# Zigbee_Tracker_v2_Mainboard.net
KiCad netlist of a schematic drawn in EAGLE
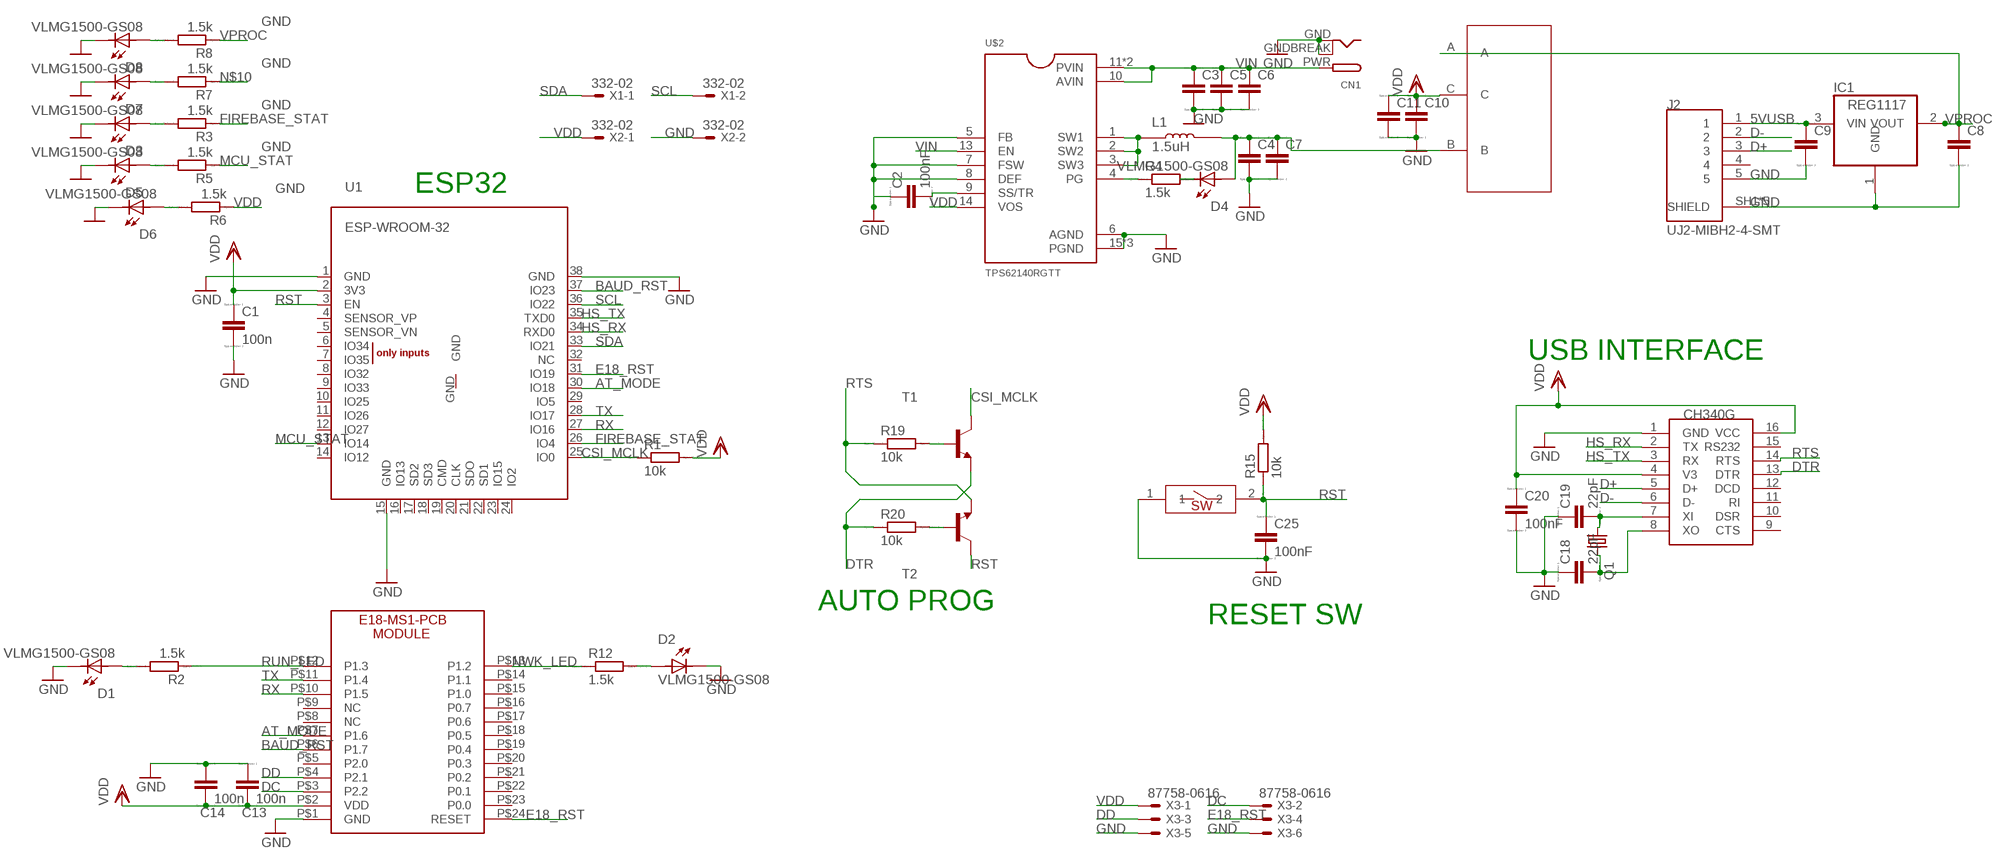
[diagram p0: schematic, sheet 1]

(export (version "E")
  (design (tool "Eeschema 10.0.6"))
  (components
    (comp (ref "C1")
      (value "100n")
      (footprint "eagle-import:C0603")
      (libsource (lib "eagle-import") (part "CC0603"))
    )
    (comp (ref "C2")
      (value "100nF")
      (footprint "eagle-import:C0402")
      (libsource (lib "eagle-import") (part "CC0402"))
    )
    (comp (ref "C3")
      (value "CC0402")
      (footprint "eagle-import:C0402")
      (libsource (lib "eagle-import") (part "CC0402"))
    )
    (comp (ref "C4")
      (value "CC0402")
      (footprint "eagle-import:C0402")
      (libsource (lib "eagle-import") (part "CC0402"))
    )
    (comp (ref "C5")
      (value "CC1210")
      (footprint "eagle-import:C1210")
      (libsource (lib "eagle-import") (part "CC1210"))
    )
    (comp (ref "C6")
      (value "CC1210")
      (footprint "eagle-import:C1210")
      (libsource (lib "eagle-import") (part "CC1210"))
    )
    (comp (ref "C7")
      (value "CC1210")
      (footprint "eagle-import:C1210")
      (libsource (lib "eagle-import") (part "CC1210"))
    )
    (comp (ref "C8")
      (value "CC0603")
      (footprint "eagle-import:C0603")
      (libsource (lib "eagle-import") (part "CC0603"))
    )
    (comp (ref "C9")
      (value "CC0603")
      (footprint "eagle-import:C0603")
      (libsource (lib "eagle-import") (part "CC0603"))
    )
    (comp (ref "C10")
      (value "CC1210")
      (footprint "eagle-import:C1210")
      (libsource (lib "eagle-import") (part "CC1210"))
    )
    (comp (ref "C11")
      (value "CC1210")
      (footprint "eagle-import:C1210")
      (libsource (lib "eagle-import") (part "CC1210"))
    )
    (comp (ref "C13")
      (value "100n")
      (footprint "eagle-import:C0603")
      (libsource (lib "eagle-import") (part "CC0603"))
    )
    (comp (ref "C14")
      (value "100n")
      (footprint "eagle-import:C0603")
      (libsource (lib "eagle-import") (part "CC0603"))
    )
    (comp (ref "C18")
      (value "22pF")
      (footprint "eagle-import:C0402")
      (libsource (lib "eagle-import") (part "CC0402"))
    )
    (comp (ref "C19")
      (value "22pF")
      (footprint "eagle-import:C0402")
      (libsource (lib "eagle-import") (part "CC0402"))
    )
    (comp (ref "C20")
      (value "100nF")
      (footprint "eagle-import:C0603")
      (libsource (lib "eagle-import") (part "CC0603"))
    )
    (comp (ref "C25")
      (value "100nF")
      (footprint "eagle-import:C0402")
      (libsource (lib "eagle-import") (part "CC0402"))
    )
    (comp (ref "CN1")
      (value "DCBARRELPTH")
      (footprint "eagle-import:DCJACK_2MM_PTH")
      (libsource (lib "eagle-import") (part "DCBARRELPTH"))
    )
    (comp (ref "D1")
      (value "VLMG1500-GS08")
      (footprint "eagle-import:LEDC1005X35N")
      (fields (field (name "MF") "Vishay"))
      (libsource (lib "eagle-import") (part "VLMG1500-GS08"))
    )
    (comp (ref "D2")
      (value "VLMG1500-GS08")
      (footprint "eagle-import:LEDC1005X35N")
      (fields (field (name "MF") "Vishay"))
      (libsource (lib "eagle-import") (part "VLMG1500-GS08"))
    )
    (comp (ref "D3")
      (value "VLMG1500-GS08")
      (footprint "eagle-import:LEDC1005X35N")
      (fields (field (name "MF") "Vishay"))
      (libsource (lib "eagle-import") (part "VLMG1500-GS08"))
    )
    (comp (ref "D4")
      (value "VLMG1500-GS08")
      (footprint "eagle-import:LEDC1005X35N")
      (fields (field (name "MF") "Vishay"))
      (libsource (lib "eagle-import") (part "VLMG1500-GS08"))
    )
    (comp (ref "D5")
      (value "VLMG1500-GS08")
      (footprint "eagle-import:LEDC1005X35N")
      (fields (field (name "MF") "Vishay"))
      (libsource (lib "eagle-import") (part "VLMG1500-GS08"))
    )
    (comp (ref "D6")
      (value "VLMG1500-GS08")
      (footprint "eagle-import:LEDC1005X35N")
      (fields (field (name "MF") "Vishay"))
      (libsource (lib "eagle-import") (part "VLMG1500-GS08"))
    )
    (comp (ref "D7")
      (value "VLMG1500-GS08")
      (footprint "eagle-import:LEDC1005X35N")
      (fields (field (name "MF") "Vishay"))
      (libsource (lib "eagle-import") (part "VLMG1500-GS08"))
    )
    (comp (ref "D8")
      (value "VLMG1500-GS08")
      (footprint "eagle-import:LEDC1005X35N")
      (fields (field (name "MF") "Vishay"))
      (libsource (lib "eagle-import") (part "VLMG1500-GS08"))
    )
    (comp (ref "IC1")
      (value "REG1117")
      (footprint "eagle-import:SOT223")
      (libsource (lib "eagle-import") (part "REG1117"))
    )
    (comp (ref "J2")
      (value "UJ2-MIBH2-4-SMT")
      (footprint "eagle-import:CUI_UJ2-MIBH2-4-SMT")
      (fields (field (name "MF") "CUI Inc."))
      (libsource (lib "eagle-import") (part "UJ2-MIBH2-4-SMT"))
    )
    (comp (ref "L1")
      (value "1.5uH")
      (footprint "eagle-import:INDC2520X120N")
      (fields (field (name "MF") "Murata Electronics") (field (name "MP") "DFE252012F-100M=P2"))
      (libsource (lib "eagle-import") (part "DFE252012F-100M=P2"))
    )
    (comp (ref "Q1")
      (value "KX-7")
      (footprint "eagle-import:3.2X2.5_KX-7")
      (libsource (lib "eagle-import") (part "KX-7"))
    )
    (comp (ref "R1")
      (value "10k")
      (footprint "eagle-import:R0402")
      (libsource (lib "eagle-import") (part "RR0402"))
    )
    (comp (ref "R2")
      (value "1.5k")
      (footprint "eagle-import:R0402")
      (libsource (lib "eagle-import") (part "RR0402"))
    )
    (comp (ref "R3")
      (value "1.5k")
      (footprint "eagle-import:R0402")
      (libsource (lib "eagle-import") (part "RR0402"))
    )
    (comp (ref "R4")
      (value "1.5k")
      (footprint "eagle-import:R0402")
      (libsource (lib "eagle-import") (part "RR0402"))
    )
    (comp (ref "R5")
      (value "1.5k")
      (footprint "eagle-import:R0402")
      (libsource (lib "eagle-import") (part "RR0402"))
    )
    (comp (ref "R6")
      (value "1.5k")
      (footprint "eagle-import:R0402")
      (libsource (lib "eagle-import") (part "RR0402"))
    )
    (comp (ref "R7")
      (value "1.5k")
      (footprint "eagle-import:R0402")
      (libsource (lib "eagle-import") (part "RR0402"))
    )
    (comp (ref "R8")
      (value "1.5k")
      (footprint "eagle-import:R0402")
      (libsource (lib "eagle-import") (part "RR0402"))
    )
    (comp (ref "R12")
      (value "1.5k")
      (footprint "eagle-import:R0402")
      (libsource (lib "eagle-import") (part "RR0402"))
    )
    (comp (ref "R15")
      (value "10k")
      (footprint "eagle-import:R0402")
      (libsource (lib "eagle-import") (part "RR0402"))
    )
    (comp (ref "R19")
      (value "10k")
      (footprint "eagle-import:R0402")
      (libsource (lib "eagle-import") (part "RR0402"))
    )
    (comp (ref "R20")
      (value "10k")
      (footprint "eagle-import:R0402")
      (libsource (lib "eagle-import") (part "RR0402"))
    )
    (comp (ref "RESET")
      (value "SMDSWITCH")
      (footprint "eagle-import:RESC4217X170")
      (libsource (lib "eagle-import") (part "SMDSWITCH"))
    )
    (comp (ref "T1")
      (value "-NPN-SOT23-BEC")
      (footprint "eagle-import:SOT23-BEC")
      (libsource (lib "eagle-import") (part "-NPN-SOT23-BEC"))
    )
    (comp (ref "T2")
      (value "-NPN-SOT23-BEC")
      (footprint "eagle-import:SOT23-BEC")
      (libsource (lib "eagle-import") (part "-NPN-SOT23-BEC"))
    )
    (comp (ref "U$1")
      (value "E18")
      (footprint "eagle-import:E18-MS1-PCB")
      (libsource (lib "eagle-import") (part "E18"))
    )
    (comp (ref "U$2")
      (value "TPS62140RGTT")
      (footprint "eagle-import:QFN50P300X300X100-17N")
      (fields (field (name "MF") "Texas Instruments"))
      (libsource (lib "eagle-import") (part "TPS62140RGTT"))
    )
    (comp (ref "U$3")
      (value "SMDTOGGLESWITCH")
      (footprint "eagle-import:SMDTOGGLESWITCH")
      (libsource (lib "eagle-import") (part "SMDTOGGLESWITCH"))
    )
    (comp (ref "U1")
      (value "ESP-WROOM-32")
      (footprint "eagle-import:ESP-WROOM-32")
      (libsource (lib "eagle-import") (part "ESP-WROOM-32"))
    )
    (comp (ref "U5")
      (value "H")
      (footprint "eagle-import:SOIC16")
      (libsource (lib "eagle-import") (part "CH340G"))
    )
    (comp (ref "X1")
      (value "332-02")
      (footprint "eagle-import:332-02")
      (libsource (lib "eagle-import") (part "332-02"))
    )
    (comp (ref "X2")
      (value "332-02")
      (footprint "eagle-import:332-02")
      (libsource (lib "eagle-import") (part "332-02"))
    )
    (comp (ref "X3")
      (value "87758-0616")
      (footprint "eagle-import:87758-0616")
      (fields (field (name "MF") "MOLEX"))
      (libsource (lib "eagle-import") (part "87758-0616"))
    )
  )
  (nets
    (net (code "1") (name "/5VUSB") (class "Default")
      (node (ref "C9") (pin "1") (pinfunction "1_1") (pintype "passive"))
      (node (ref "IC1") (pin "3") (pinfunction "VIN_3") (pintype "input"))
      (node (ref "J2") (pin "1") (pinfunction "1_1") (pintype "passive"))
    )
    (net (code "2") (name "/AT_MODE") (class "Default")
      (node (ref "U$1") (pin "P$7") (pinfunction "P1.6_P$7") (pintype "bidirectional"))
      (node (ref "U1") (pin "30") (pinfunction "IO18_30") (pintype "bidirectional"))
    )
    (net (code "3") (name "/BAUD_RST") (class "Default")
      (node (ref "U$1") (pin "P$6") (pinfunction "P1.7_P$6") (pintype "bidirectional"))
      (node (ref "U1") (pin "37") (pinfunction "IO23_37") (pintype "bidirectional"))
    )
    (net (code "4") (name "/CSI_MCLK") (class "Default")
      (node (ref "R1") (pin "1") (pinfunction "1_1") (pintype "passive"))
      (node (ref "T1") (pin "C") (pinfunction "C_C") (pintype "passive"))
      (node (ref "U1") (pin "25") (pinfunction "IO0_25") (pintype "bidirectional"))
    )
    (net (code "5") (name "/D+") (class "Default")
      (node (ref "J2") (pin "3") (pinfunction "3_3") (pintype "passive"))
      (node (ref "U5") (pin "5") (pinfunction "D+_5") (pintype "bidirectional"))
    )
    (net (code "6") (name "/D-") (class "Default")
      (node (ref "J2") (pin "2") (pinfunction "2_2") (pintype "passive"))
      (node (ref "U5") (pin "6") (pinfunction "D-_6") (pintype "bidirectional"))
    )
    (net (code "7") (name "/DC") (class "Default")
      (node (ref "U$1") (pin "P$3") (pinfunction "P2.2_P$3") (pintype "bidirectional"))
      (node (ref "X3") (pin "2") (pinfunction "S_2") (pintype "passive"))
    )
    (net (code "8") (name "/DD") (class "Default")
      (node (ref "U$1") (pin "P$4") (pinfunction "P2.1_P$4") (pintype "bidirectional"))
      (node (ref "X3") (pin "3") (pinfunction "S_3") (pintype "passive"))
    )
    (net (code "9") (name "/DTR") (class "Default")
      (node (ref "R20") (pin "1") (pinfunction "1_1") (pintype "passive"))
      (node (ref "T1") (pin "E") (pinfunction "E_E") (pintype "passive"))
      (node (ref "U5") (pin "13") (pinfunction "DTR_13") (pintype "bidirectional"))
    )
    (net (code "10") (name "/E18_RST") (class "Default")
      (node (ref "U$1") (pin "P$24") (pinfunction "RESET_P$24") (pintype "bidirectional"))
      (node (ref "U1") (pin "31") (pinfunction "IO19_31") (pintype "bidirectional"))
      (node (ref "X3") (pin "4") (pinfunction "S_4") (pintype "passive"))
    )
    (net (code "11") (name "/FIREBASE_STAT") (class "Default")
      (node (ref "R3") (pin "1") (pinfunction "1_1") (pintype "passive"))
      (node (ref "U1") (pin "26") (pinfunction "IO4_26") (pintype "bidirectional"))
    )
    (net (code "12") (name "/HS_RX") (class "Default")
      (node (ref "U1") (pin "34") (pinfunction "RXD0_34") (pintype "bidirectional"))
      (node (ref "U5") (pin "2") (pinfunction "TX_2") (pintype "bidirectional"))
    )
    (net (code "13") (name "/HS_TX") (class "Default")
      (node (ref "U1") (pin "35") (pinfunction "TXD0_35") (pintype "bidirectional"))
      (node (ref "U5") (pin "3") (pinfunction "RX_3") (pintype "bidirectional"))
    )
    (net (code "14") (name "/MCU_STAT") (class "Default")
      (node (ref "R5") (pin "1") (pinfunction "1_1") (pintype "passive"))
      (node (ref "U1") (pin "13") (pinfunction "IO14_13") (pintype "bidirectional"))
    )
    (net (code "15") (name "/N$10") (class "Default")
      (node (ref "C4") (pin "1") (pinfunction "1_1") (pintype "passive"))
      (node (ref "C7") (pin "1") (pinfunction "1_1") (pintype "passive"))
      (node (ref "D4") (pin "1") (pinfunction "1_1") (pintype "passive"))
      (node (ref "L1") (pin "2") (pinfunction "2_2") (pintype "passive"))
      (node (ref "R7") (pin "1") (pinfunction "1_1") (pintype "passive"))
      (node (ref "U$3") (pin "B") (pinfunction "B_B") (pintype "bidirectional"))
    )
    (net (code "16") (name "/NWK_LED") (class "Default")
      (node (ref "R12") (pin "1") (pinfunction "1_1") (pintype "passive"))
      (node (ref "U$1") (pin "P$13") (pinfunction "P1.2_P$13") (pintype "bidirectional"))
    )
    (net (code "17") (name "/RST") (class "Default")
      (node (ref "C25") (pin "1") (pinfunction "1_1") (pintype "passive"))
      (node (ref "R15") (pin "1") (pinfunction "1_1") (pintype "passive"))
      (node (ref "RESET") (pin "2") (pinfunction "2_2") (pintype "bidirectional"))
      (node (ref "T2") (pin "C") (pinfunction "C_C") (pintype "passive"))
      (node (ref "U1") (pin "3") (pinfunction "EN_3") (pintype "bidirectional"))
    )
    (net (code "18") (name "/RTS") (class "Default")
      (node (ref "R19") (pin "1") (pinfunction "1_1") (pintype "passive"))
      (node (ref "T2") (pin "E") (pinfunction "E_E") (pintype "passive"))
      (node (ref "U5") (pin "14") (pinfunction "RTS_14") (pintype "bidirectional"))
    )
    (net (code "19") (name "/RUN_LED") (class "Default")
      (node (ref "R2") (pin "1") (pinfunction "1_1") (pintype "passive"))
      (node (ref "U$1") (pin "P$12") (pinfunction "P1.3_P$12") (pintype "bidirectional"))
    )
    (net (code "20") (name "/RX") (class "Default")
      (node (ref "U$1") (pin "P$10") (pinfunction "P1.5_P$10") (pintype "bidirectional"))
      (node (ref "U1") (pin "27") (pinfunction "IO16_27") (pintype "bidirectional"))
    )
    (net (code "21") (name "/SCL") (class "Default")
      (node (ref "U1") (pin "36") (pinfunction "IO22_36") (pintype "bidirectional"))
      (node (ref "X1") (pin "2") (pinfunction "S_2") (pintype "passive"))
    )
    (net (code "22") (name "/SDA") (class "Default")
      (node (ref "U1") (pin "33") (pinfunction "IO21_33") (pintype "bidirectional"))
      (node (ref "X1") (pin "1") (pinfunction "S_1") (pintype "passive"))
    )
    (net (code "23") (name "/TX") (class "Default")
      (node (ref "U$1") (pin "P$11") (pinfunction "P1.4_P$11") (pintype "bidirectional"))
      (node (ref "U1") (pin "28") (pinfunction "IO17_28") (pintype "bidirectional"))
    )
    (net (code "24") (name "/VIN") (class "Default")
      (node (ref "C3") (pin "1") (pinfunction "1_1") (pintype "passive"))
      (node (ref "C5") (pin "1") (pinfunction "1_1") (pintype "passive"))
      (node (ref "C6") (pin "1") (pinfunction "1_1") (pintype "passive"))
      (node (ref "CN1") (pin "PWR") (pinfunction "PWR_PWR") (pintype "power_in"))
      (node (ref "U$2") (pin "10") (pinfunction "AVIN_10") (pintype "power_in"))
      (node (ref "U$2") (pin "11") (pinfunction "PVIN_11") (pintype "power_in"))
      (node (ref "U$2") (pin "12") (pinfunction "PVIN_12") (pintype "power_in"))
      (node (ref "U$2") (pin "13") (pinfunction "EN_13") (pintype "input"))
    )
    (net (code "25") (name "/VPROC") (class "Default")
      (node (ref "C8") (pin "1") (pinfunction "1_1") (pintype "passive"))
      (node (ref "IC1") (pin "2") (pinfunction "VOUT_2") (pintype "output"))
      (node (ref "R8") (pin "1") (pinfunction "1_1") (pintype "passive"))
      (node (ref "U$3") (pin "A") (pinfunction "A_A") (pintype "bidirectional"))
    )
    (net (code "26") (name "GND") (class "Default")
      (node (ref "C1") (pin "2") (pinfunction "2_2") (pintype "passive"))
      (node (ref "C10") (pin "2") (pinfunction "2_2") (pintype "passive"))
      (node (ref "C11") (pin "2") (pinfunction "2_2") (pintype "passive"))
      (node (ref "C13") (pin "1") (pinfunction "1_1") (pintype "passive"))
      (node (ref "C14") (pin "1") (pinfunction "1_1") (pintype "passive"))
      (node (ref "C18") (pin "1") (pinfunction "1_1") (pintype "passive"))
      (node (ref "C19") (pin "1") (pinfunction "1_1") (pintype "passive"))
      (node (ref "C2") (pin "1") (pinfunction "1_1") (pintype "passive"))
      (node (ref "C20") (pin "2") (pinfunction "2_2") (pintype "passive"))
      (node (ref "C25") (pin "2") (pinfunction "2_2") (pintype "passive"))
      (node (ref "C3") (pin "2") (pinfunction "2_2") (pintype "passive"))
      (node (ref "C4") (pin "2") (pinfunction "2_2") (pintype "passive"))
      (node (ref "C5") (pin "2") (pinfunction "2_2") (pintype "passive"))
      (node (ref "C6") (pin "2") (pinfunction "2_2") (pintype "passive"))
      (node (ref "C7") (pin "2") (pinfunction "2_2") (pintype "passive"))
      (node (ref "C8") (pin "2") (pinfunction "2_2") (pintype "passive"))
      (node (ref "C9") (pin "2") (pinfunction "2_2") (pintype "passive"))
      (node (ref "CN1") (pin "GND") (pinfunction "GND_GND") (pintype "power_in"))
      (node (ref "CN1") (pin "GNDBREAK") (pinfunction "GNDBREAK_GNDBREAK") (pintype "power_in"))
      (node (ref "D1") (pin "2") (pinfunction "2_2") (pintype "passive"))
      (node (ref "D2") (pin "2") (pinfunction "2_2") (pintype "passive"))
      (node (ref "D3") (pin "2") (pinfunction "2_2") (pintype "passive"))
      (node (ref "D5") (pin "2") (pinfunction "2_2") (pintype "passive"))
      (node (ref "D6") (pin "2") (pinfunction "2_2") (pintype "passive"))
      (node (ref "D7") (pin "2") (pinfunction "2_2") (pintype "passive"))
      (node (ref "D8") (pin "2") (pinfunction "2_2") (pintype "passive"))
      (node (ref "IC1") (pin "1") (pinfunction "GND_1") (pintype "power_in"))
      (node (ref "J2") (pin "5") (pinfunction "5_5") (pintype "passive"))
      (node (ref "J2") (pin "SH1") (pinfunction "SHIELD_SH1") (pintype "passive"))
      (node (ref "J2") (pin "SH2") (pinfunction "SHIELD_SH2") (pintype "passive"))
      (node (ref "J2") (pin "SH3") (pinfunction "SHIELD_SH3") (pintype "passive"))
      (node (ref "J2") (pin "SH4") (pinfunction "SHIELD_SH4") (pintype "passive"))
      (node (ref "J2") (pin "SH5") (pinfunction "SHIELD_SH5") (pintype "passive"))
      (node (ref "RESET") (pin "1") (pinfunction "1_1") (pintype "bidirectional"))
      (node (ref "U$1") (pin "P$1") (pinfunction "GND_P$1") (pintype "bidirectional"))
      (node (ref "U$2") (pin "15") (pinfunction "PGND_15") (pintype "passive"))
      (node (ref "U$2") (pin "16") (pinfunction "PGND_16") (pintype "passive"))
      (node (ref "U$2") (pin "5") (pinfunction "FB_5") (pintype "input"))
      (node (ref "U$2") (pin "6") (pinfunction "AGND_6") (pintype "passive"))
      (node (ref "U$2") (pin "7") (pinfunction "FSW_7") (pintype "input"))
      (node (ref "U$2") (pin "8") (pinfunction "DEF_8") (pintype "input"))
      (node (ref "U$2") (pin "TH") (pinfunction "PGND_TH") (pintype "passive"))
      (node (ref "U1") (pin "1") (pinfunction "GND_1") (pintype "bidirectional"))
      (node (ref "U1") (pin "15") (pinfunction "GND_15") (pintype "bidirectional"))
      (node (ref "U1") (pin "38") (pinfunction "GND_38") (pintype "bidirectional"))
      (node (ref "U5") (pin "1") (pinfunction "GND_1") (pintype "bidirectional"))
      (node (ref "X2") (pin "2") (pinfunction "S_2") (pintype "passive"))
      (node (ref "X3") (pin "5") (pinfunction "S_5") (pintype "passive"))
      (node (ref "X3") (pin "6") (pinfunction "S_6") (pintype "passive"))
    )
    (net (code "27") (name "Net-(D1-Pad1)") (class "Default")
      (node (ref "D1") (pin "1") (pinfunction "1_1") (pintype "passive"))
      (node (ref "R2") (pin "2") (pinfunction "2_2") (pintype "passive"))
    )
    (net (code "28") (name "Net-(D2-Pad1)") (class "Default")
      (node (ref "D2") (pin "1") (pinfunction "1_1") (pintype "passive"))
      (node (ref "R12") (pin "2") (pinfunction "2_2") (pintype "passive"))
    )
    (net (code "29") (name "Net-(D3-Pad1)") (class "Default")
      (node (ref "D3") (pin "1") (pinfunction "1_1") (pintype "passive"))
      (node (ref "R3") (pin "2") (pinfunction "2_2") (pintype "passive"))
    )
    (net (code "30") (name "Net-(D4-Pad2)") (class "Default")
      (node (ref "D4") (pin "2") (pinfunction "2_2") (pintype "passive"))
      (node (ref "R4") (pin "2") (pinfunction "2_2") (pintype "passive"))
    )
    (net (code "31") (name "Net-(D5-Pad1)") (class "Default")
      (node (ref "D5") (pin "1") (pinfunction "1_1") (pintype "passive"))
      (node (ref "R5") (pin "2") (pinfunction "2_2") (pintype "passive"))
    )
    (net (code "32") (name "Net-(D6-Pad1)") (class "Default")
      (node (ref "D6") (pin "1") (pinfunction "1_1") (pintype "passive"))
      (node (ref "R6") (pin "2") (pinfunction "2_2") (pintype "passive"))
    )
    (net (code "33") (name "Net-(D7-Pad1)") (class "Default")
      (node (ref "D7") (pin "1") (pinfunction "1_1") (pintype "passive"))
      (node (ref "R7") (pin "2") (pinfunction "2_2") (pintype "passive"))
    )
    (net (code "34") (name "Net-(D8-Pad1)") (class "Default")
      (node (ref "D8") (pin "1") (pinfunction "1_1") (pintype "passive"))
      (node (ref "R8") (pin "2") (pinfunction "2_2") (pintype "passive"))
    )
    (net (code "35") (name "Net-(Q1-2)") (class "Default")
      (node (ref "C18") (pin "2") (pinfunction "2_2") (pintype "passive"))
      (node (ref "Q1") (pin "3") (pinfunction "2_3") (pintype "passive"))
      (node (ref "U5") (pin "8") (pinfunction "XO_8") (pintype "bidirectional"))
    )
    (net (code "36") (name "Net-(R19-Pad2)") (class "Default")
      (node (ref "R19") (pin "2") (pinfunction "2_2") (pintype "passive"))
      (node (ref "T1") (pin "B") (pinfunction "B_B") (pintype "passive"))
    )
    (net (code "37") (name "Net-(R20-Pad2)") (class "Default")
      (node (ref "R20") (pin "2") (pinfunction "2_2") (pintype "passive"))
      (node (ref "T2") (pin "B") (pinfunction "B_B") (pintype "passive"))
    )
    (net (code "38") (name "Net-(U$2-PG)") (class "Default")
      (node (ref "R4") (pin "1") (pinfunction "1_1") (pintype "passive"))
      (node (ref "U$2") (pin "4") (pinfunction "PG_4") (pintype "output"))
    )
    (net (code "39") (name "Net-(U$2-SS{slash}TR)") (class "Default")
      (node (ref "C2") (pin "2") (pinfunction "2_2") (pintype "passive"))
      (node (ref "U$2") (pin "9") (pinfunction "SS/TR_9") (pintype "input"))
    )
    (net (code "40") (name "Net-(U$2-SW1)") (class "Default")
      (node (ref "L1") (pin "1") (pinfunction "1_1") (pintype "passive"))
      (node (ref "U$2") (pin "1") (pinfunction "SW1_1") (pintype "output"))
      (node (ref "U$2") (pin "2") (pinfunction "SW2_2") (pintype "output"))
      (node (ref "U$2") (pin "3") (pinfunction "SW3_3") (pintype "output"))
    )
    (net (code "41") (name "Net-(U5-XI)") (class "Default")
      (node (ref "C19") (pin "2") (pinfunction "2_2") (pintype "passive"))
      (node (ref "Q1") (pin "1") (pinfunction "1_1") (pintype "passive"))
      (node (ref "U5") (pin "7") (pinfunction "XI_7") (pintype "bidirectional"))
    )
    (net (code "42") (name "VDD") (class "Default")
      (node (ref "C1") (pin "1") (pinfunction "1_1") (pintype "passive"))
      (node (ref "C10") (pin "1") (pinfunction "1_1") (pintype "passive"))
      (node (ref "C11") (pin "1") (pinfunction "1_1") (pintype "passive"))
      (node (ref "C13") (pin "2") (pinfunction "2_2") (pintype "passive"))
      (node (ref "C14") (pin "2") (pinfunction "2_2") (pintype "passive"))
      (node (ref "C20") (pin "1") (pinfunction "1_1") (pintype "passive"))
      (node (ref "R1") (pin "2") (pinfunction "2_2") (pintype "passive"))
      (node (ref "R15") (pin "2") (pinfunction "2_2") (pintype "passive"))
      (node (ref "R6") (pin "1") (pinfunction "1_1") (pintype "passive"))
      (node (ref "U$1") (pin "P$2") (pinfunction "VDD_P$2") (pintype "bidirectional"))
      (node (ref "U$2") (pin "14") (pinfunction "VOS_14") (pintype "input"))
      (node (ref "U$3") (pin "C") (pinfunction "C_C") (pintype "bidirectional"))
      (node (ref "U1") (pin "2") (pinfunction "3V3_2") (pintype "bidirectional"))
      (node (ref "U5") (pin "16") (pinfunction "VCC_16") (pintype "bidirectional"))
      (node (ref "U5") (pin "4") (pinfunction "V3_4") (pintype "bidirectional"))
      (node (ref "X2") (pin "1") (pinfunction "S_1") (pintype "passive"))
      (node (ref "X3") (pin "1") (pinfunction "S_1") (pintype "passive"))
    )
    (net (code "43") (name "unconnected-(J2-Pad4)") (class "Default")
      (node (ref "J2") (pin "4") (pinfunction "4_4") (pintype "passive"))
    )
    (net (code "44") (name "unconnected-(U$1-NC-PadP$8)") (class "Default")
      (node (ref "U$1") (pin "P$8") (pinfunction "NC_P$8") (pintype "bidirectional"))
    )
    (net (code "45") (name "unconnected-(U$1-NC-PadP$9)") (class "Default")
      (node (ref "U$1") (pin "P$9") (pinfunction "NC_P$9") (pintype "bidirectional"))
    )
    (net (code "46") (name "unconnected-(U$1-P0.0-PadP$23)") (class "Default")
      (node (ref "U$1") (pin "P$23") (pinfunction "P0.0_P$23") (pintype "bidirectional"))
    )
    (net (code "47") (name "unconnected-(U$1-P0.1-PadP$22)") (class "Default")
      (node (ref "U$1") (pin "P$22") (pinfunction "P0.1_P$22") (pintype "bidirectional"))
    )
    (net (code "48") (name "unconnected-(U$1-P0.2-PadP$21)") (class "Default")
      (node (ref "U$1") (pin "P$21") (pinfunction "P0.2_P$21") (pintype "bidirectional"))
    )
    (net (code "49") (name "unconnected-(U$1-P0.3-PadP$20)") (class "Default")
      (node (ref "U$1") (pin "P$20") (pinfunction "P0.3_P$20") (pintype "bidirectional"))
    )
    (net (code "50") (name "unconnected-(U$1-P0.4-PadP$19)") (class "Default")
      (node (ref "U$1") (pin "P$19") (pinfunction "P0.4_P$19") (pintype "bidirectional"))
    )
    (net (code "51") (name "unconnected-(U$1-P0.5-PadP$18)") (class "Default")
      (node (ref "U$1") (pin "P$18") (pinfunction "P0.5_P$18") (pintype "bidirectional"))
    )
    (net (code "52") (name "unconnected-(U$1-P0.6-PadP$17)") (class "Default")
      (node (ref "U$1") (pin "P$17") (pinfunction "P0.6_P$17") (pintype "bidirectional"))
    )
    (net (code "53") (name "unconnected-(U$1-P0.7-PadP$16)") (class "Default")
      (node (ref "U$1") (pin "P$16") (pinfunction "P0.7_P$16") (pintype "bidirectional"))
    )
    (net (code "54") (name "unconnected-(U$1-P1.0-PadP$15)") (class "Default")
      (node (ref "U$1") (pin "P$15") (pinfunction "P1.0_P$15") (pintype "bidirectional"))
    )
    (net (code "55") (name "unconnected-(U$1-P1.1-PadP$14)") (class "Default")
      (node (ref "U$1") (pin "P$14") (pinfunction "P1.1_P$14") (pintype "bidirectional"))
    )
    (net (code "56") (name "unconnected-(U$1-P2.0-PadP$5)") (class "Default")
      (node (ref "U$1") (pin "P$5") (pinfunction "P2.0_P$5") (pintype "bidirectional"))
    )
    (net (code "57") (name "unconnected-(U1-CLK-Pad20)") (class "Default")
      (node (ref "U1") (pin "20") (pinfunction "CLK_20") (pintype "bidirectional"))
    )
    (net (code "58") (name "unconnected-(U1-CMD-Pad19)") (class "Default")
      (node (ref "U1") (pin "19") (pinfunction "CMD_19") (pintype "bidirectional"))
    )
    (net (code "59") (name "unconnected-(U1-IO2-Pad24)") (class "Default")
      (node (ref "U1") (pin "24") (pinfunction "IO2_24") (pintype "bidirectional"))
    )
    (net (code "60") (name "unconnected-(U1-IO5-Pad29)") (class "Default")
      (node (ref "U1") (pin "29") (pinfunction "IO5_29") (pintype "bidirectional"))
    )
    (net (code "61") (name "unconnected-(U1-IO12-Pad14)") (class "Default")
      (node (ref "U1") (pin "14") (pinfunction "IO12_14") (pintype "bidirectional"))
    )
    (net (code "62") (name "unconnected-(U1-IO13-Pad16)") (class "Default")
      (node (ref "U1") (pin "16") (pinfunction "IO13_16") (pintype "bidirectional"))
    )
    (net (code "63") (name "unconnected-(U1-IO15-Pad23)") (class "Default")
      (node (ref "U1") (pin "23") (pinfunction "IO15_23") (pintype "bidirectional"))
    )
    (net (code "64") (name "unconnected-(U1-IO25-Pad10)") (class "Default")
      (node (ref "U1") (pin "10") (pinfunction "IO25_10") (pintype "bidirectional"))
    )
    (net (code "65") (name "unconnected-(U1-IO26-Pad11)") (class "Default")
      (node (ref "U1") (pin "11") (pinfunction "IO26_11") (pintype "bidirectional"))
    )
    (net (code "66") (name "unconnected-(U1-IO27-Pad12)") (class "Default")
      (node (ref "U1") (pin "12") (pinfunction "IO27_12") (pintype "bidirectional"))
    )
    (net (code "67") (name "unconnected-(U1-IO32-Pad8)") (class "Default")
      (node (ref "U1") (pin "8") (pinfunction "IO32_8") (pintype "bidirectional"))
    )
    (net (code "68") (name "unconnected-(U1-IO33-Pad9)") (class "Default")
      (node (ref "U1") (pin "9") (pinfunction "IO33_9") (pintype "bidirectional"))
    )
    (net (code "69") (name "unconnected-(U1-IO34-Pad6)") (class "Default")
      (node (ref "U1") (pin "6") (pinfunction "IO34_6") (pintype "input"))
    )
    (net (code "70") (name "unconnected-(U1-IO35-Pad7)") (class "Default")
      (node (ref "U1") (pin "7") (pinfunction "IO35_7") (pintype "input"))
    )
    (net (code "71") (name "unconnected-(U1-NC-Pad32)") (class "Default")
      (node (ref "U1") (pin "32") (pinfunction "NC_32") (pintype "bidirectional"))
    )
    (net (code "72") (name "unconnected-(U1-PadGND)") (class "Default")
      (node (ref "U1") (pin "GND") (pinfunction "GND_GND") (pintype "bidirectional"))
    )
    (net (code "73") (name "unconnected-(U1-SD1-Pad22)") (class "Default")
      (node (ref "U1") (pin "22") (pinfunction "SD1_22") (pintype "bidirectional"))
    )
    (net (code "74") (name "unconnected-(U1-SD2-Pad17)") (class "Default")
      (node (ref "U1") (pin "17") (pinfunction "SD2_17") (pintype "bidirectional"))
    )
    (net (code "75") (name "unconnected-(U1-SD3-Pad18)") (class "Default")
      (node (ref "U1") (pin "18") (pinfunction "SD3_18") (pintype "bidirectional"))
    )
    (net (code "76") (name "unconnected-(U1-SDO-Pad21)") (class "Default")
      (node (ref "U1") (pin "21") (pinfunction "SDO_21") (pintype "bidirectional"))
    )
    (net (code "77") (name "unconnected-(U1-SENSOR_VN-Pad5)") (class "Default")
      (node (ref "U1") (pin "5") (pinfunction "SENSOR_VN_5") (pintype "input"))
    )
    (net (code "78") (name "unconnected-(U1-SENSOR_VP-Pad4)") (class "Default")
      (node (ref "U1") (pin "4") (pinfunction "SENSOR_VP_4") (pintype "input"))
    )
    (net (code "79") (name "unconnected-(U5-CTS-Pad9)") (class "Default")
      (node (ref "U5") (pin "9") (pinfunction "CTS_9") (pintype "bidirectional"))
    )
    (net (code "80") (name "unconnected-(U5-DCD-Pad12)") (class "Default")
      (node (ref "U5") (pin "12") (pinfunction "DCD_12") (pintype "bidirectional"))
    )
    (net (code "81") (name "unconnected-(U5-DSR-Pad10)") (class "Default")
      (node (ref "U5") (pin "10") (pinfunction "DSR_10") (pintype "bidirectional"))
    )
    (net (code "82") (name "unconnected-(U5-RI-Pad11)") (class "Default")
      (node (ref "U5") (pin "11") (pinfunction "RI_11") (pintype "bidirectional"))
    )
    (net (code "83") (name "unconnected-(U5-RS232-Pad15)") (class "Default")
      (node (ref "U5") (pin "15") (pinfunction "RS232_15") (pintype "bidirectional"))
    )
  )
)
